# axiom_beta_shield_HDMI_v0_2_b03618a9.net
KiCad netlist of a schematic drawn in EAGLE
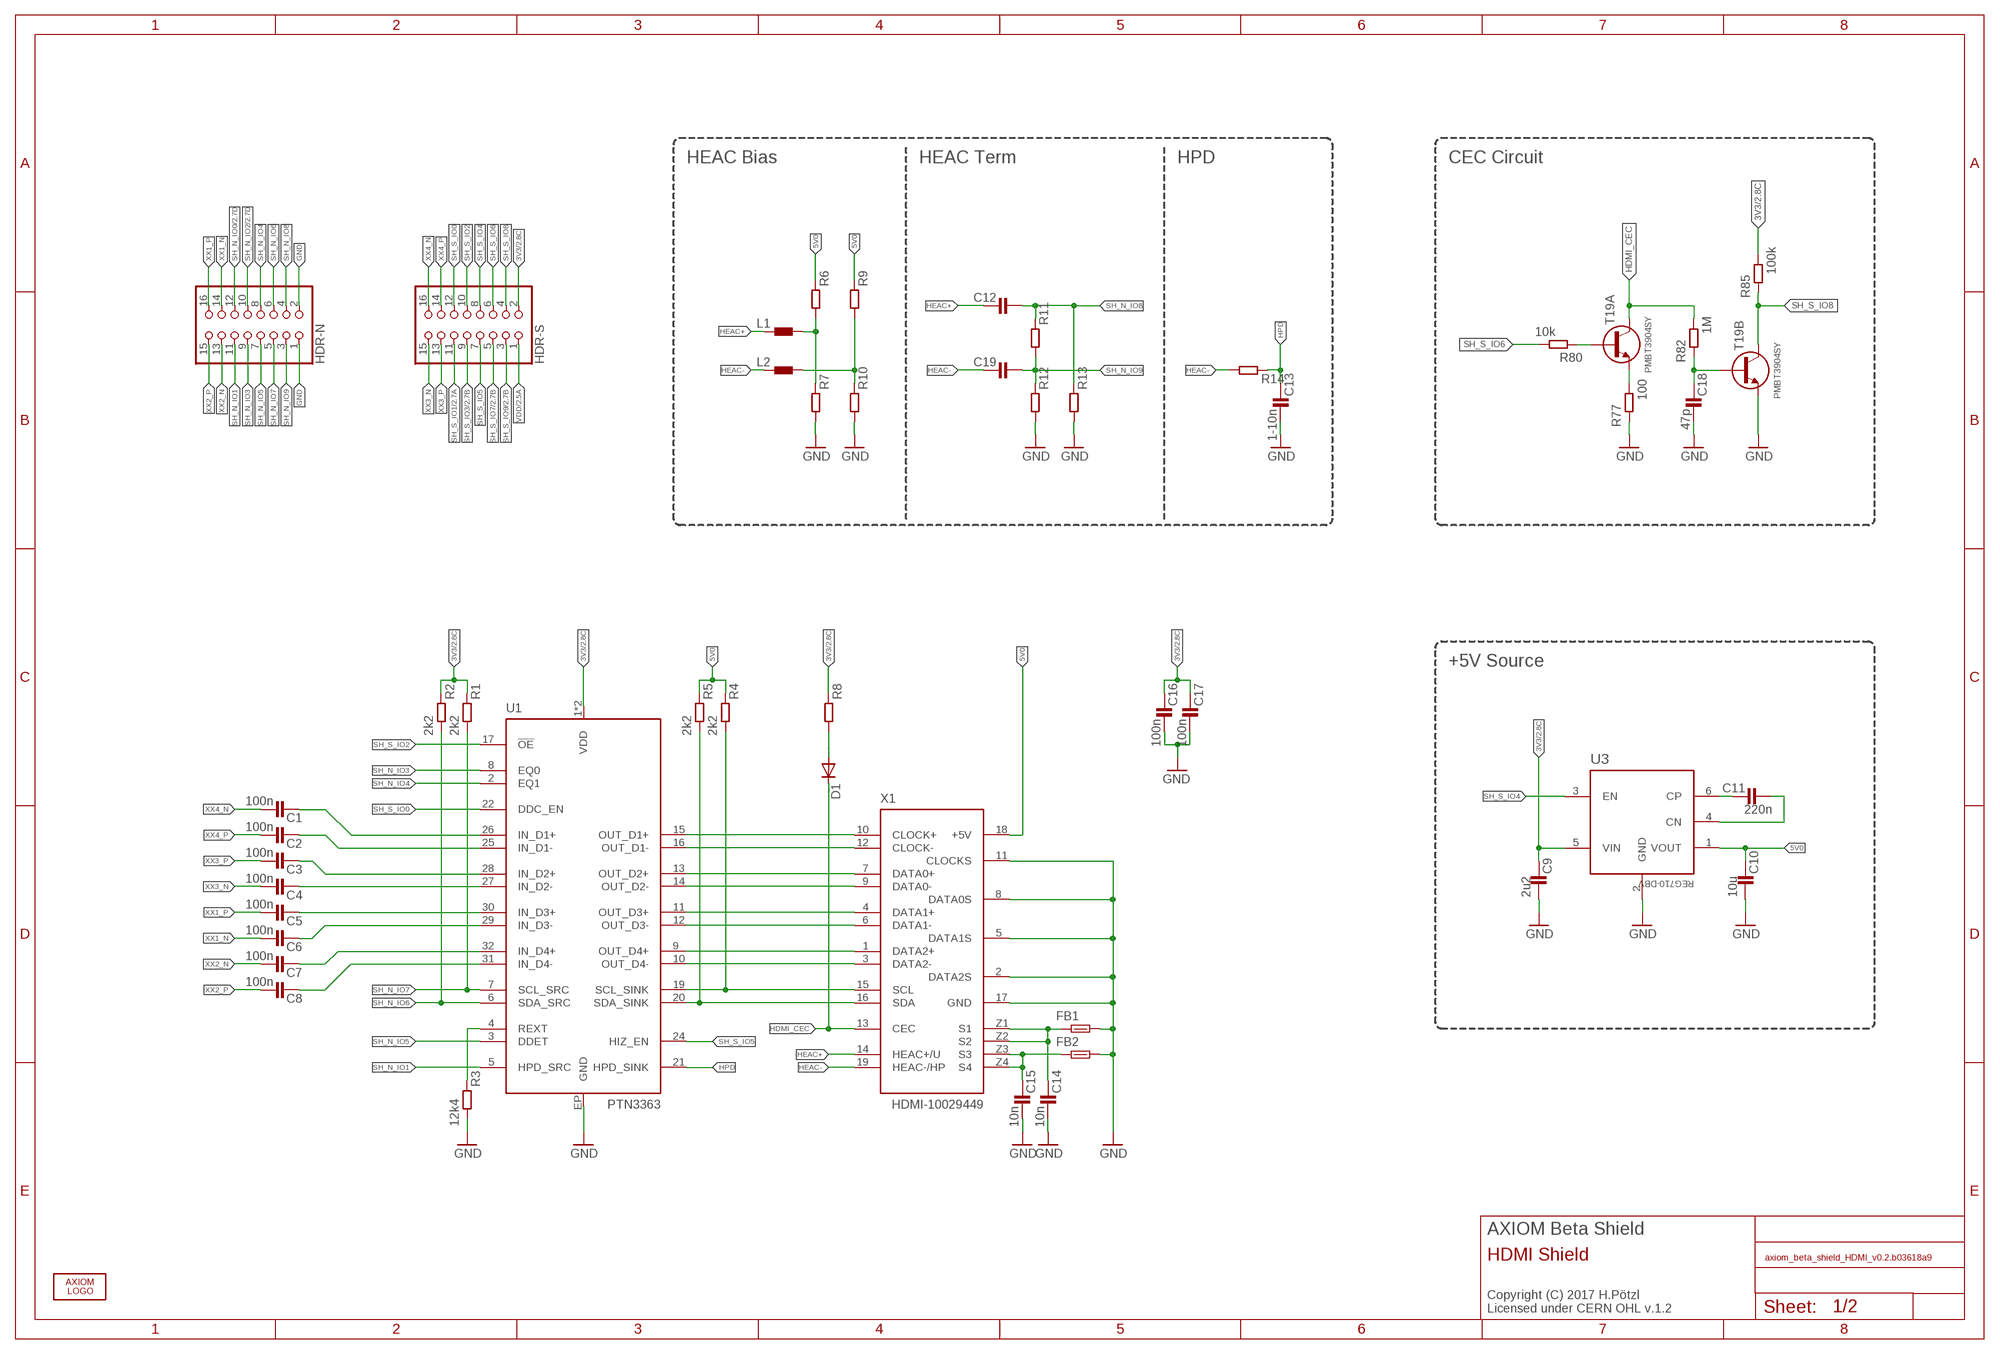
[diagram p0: schematic, sheet 1]
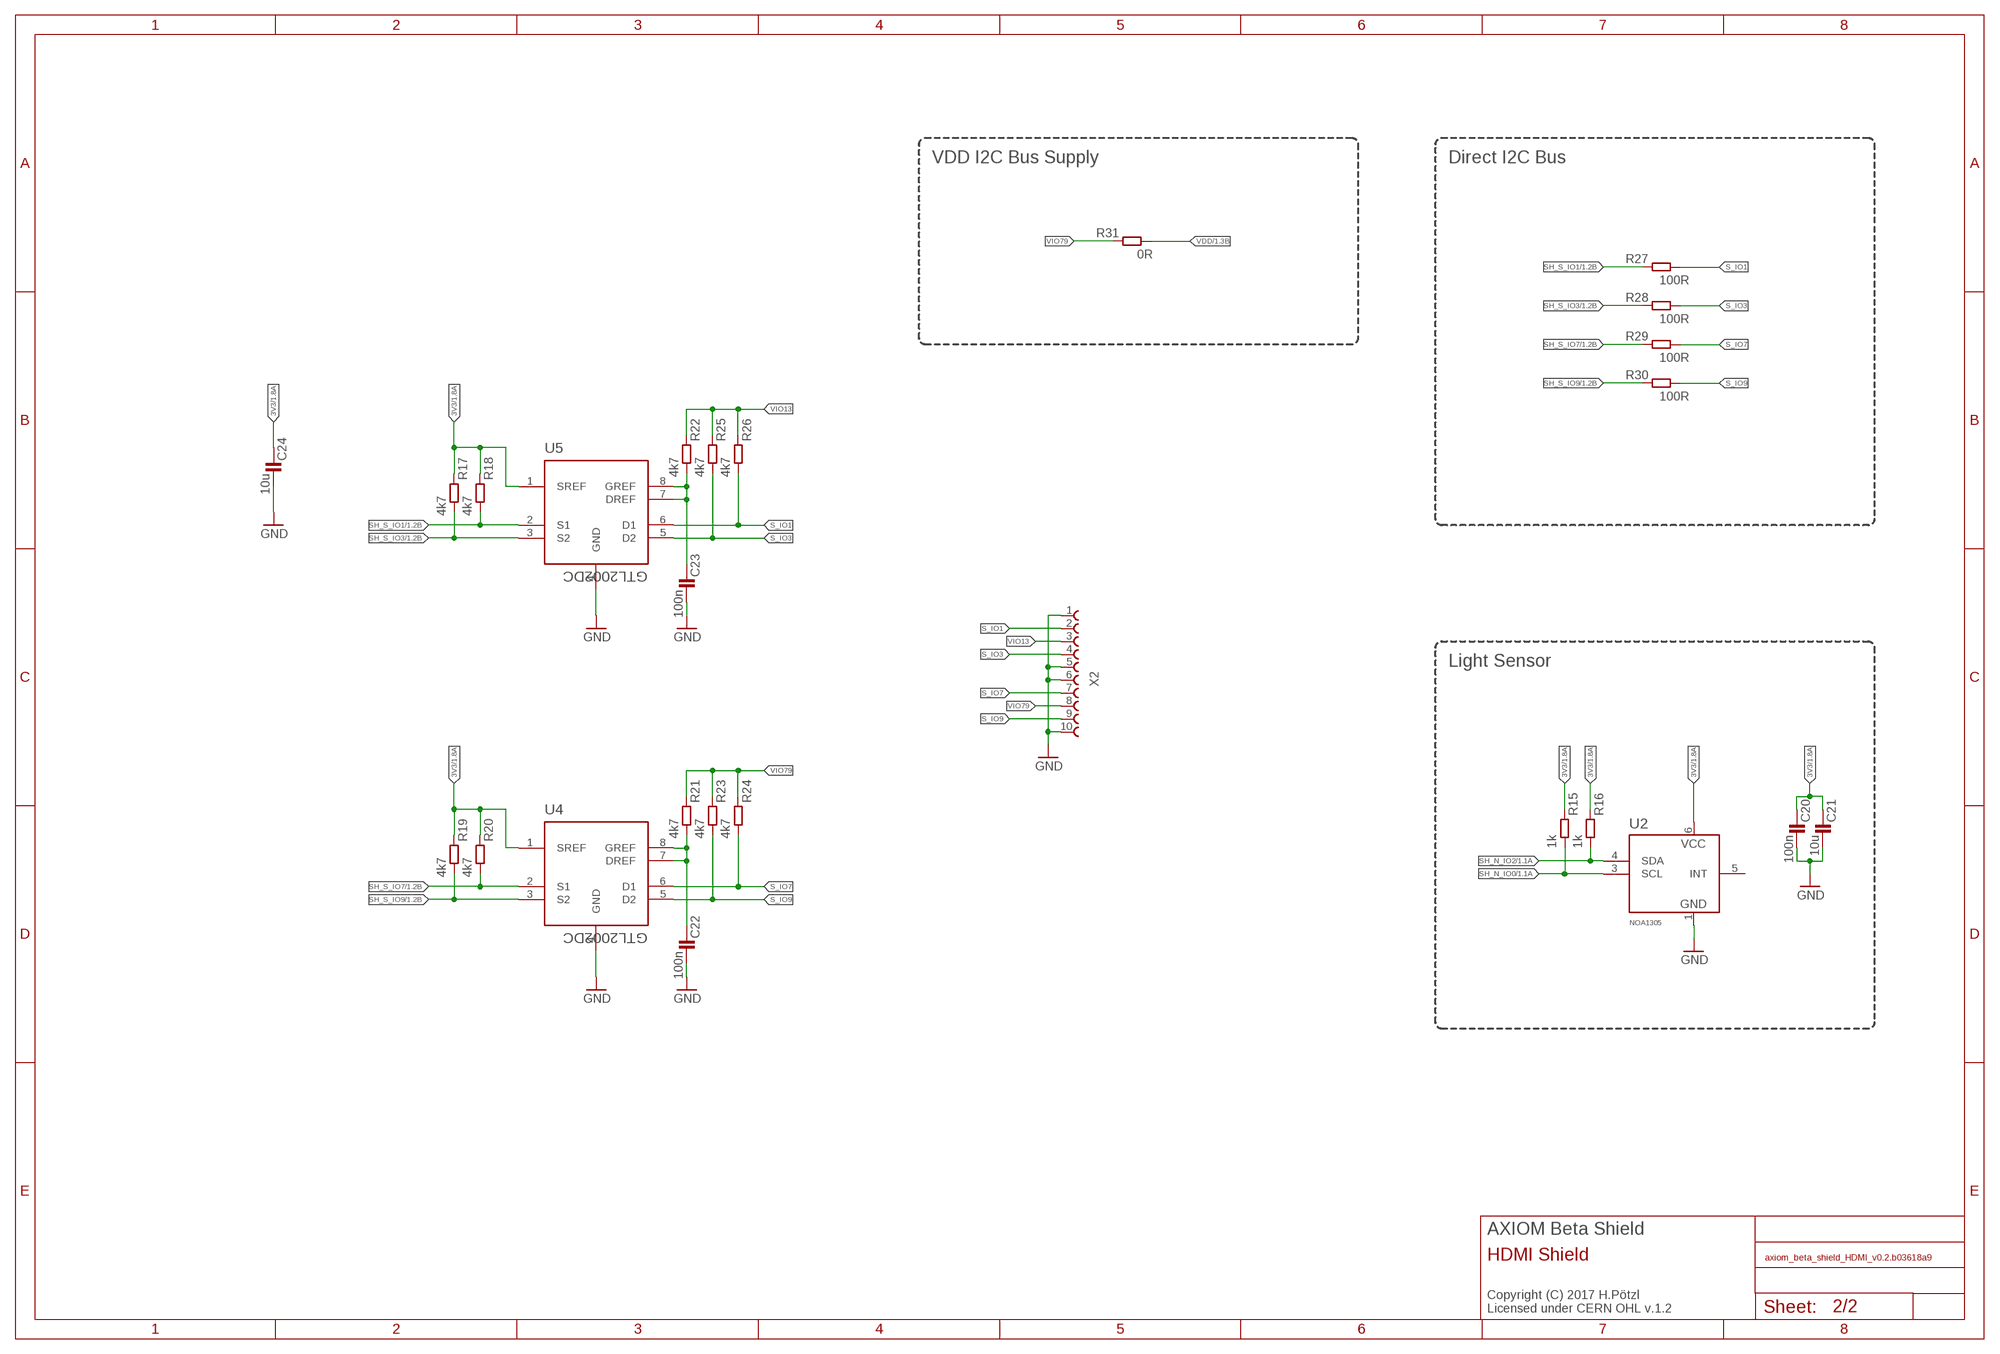
[diagram p1: schematic, sheet 2]

(export (version "E")
  (design (tool "Eeschema 10.0.6"))
  (components
    (comp (ref "C1")
      (value "100n")
      (footprint "eagle-import:0402-C")
      (libsource (lib "eagle-import") (part "C0402-C"))
    )
    (comp (ref "C2")
      (value "100n")
      (footprint "eagle-import:0402-C")
      (libsource (lib "eagle-import") (part "C0402-C"))
    )
    (comp (ref "C3")
      (value "100n")
      (footprint "eagle-import:0402-C")
      (libsource (lib "eagle-import") (part "C0402-C"))
    )
    (comp (ref "C4")
      (value "100n")
      (footprint "eagle-import:0402-C")
      (libsource (lib "eagle-import") (part "C0402-C"))
    )
    (comp (ref "C5")
      (value "100n")
      (footprint "eagle-import:0402-C")
      (libsource (lib "eagle-import") (part "C0402-C"))
    )
    (comp (ref "C6")
      (value "100n")
      (footprint "eagle-import:0402-C")
      (libsource (lib "eagle-import") (part "C0402-C"))
    )
    (comp (ref "C7")
      (value "100n")
      (footprint "eagle-import:0402-C")
      (libsource (lib "eagle-import") (part "C0402-C"))
    )
    (comp (ref "C8")
      (value "100n")
      (footprint "eagle-import:0402-C")
      (libsource (lib "eagle-import") (part "C0402-C"))
    )
    (comp (ref "C9")
      (value "2u2")
      (footprint "eagle-import:0603-B")
      (libsource (lib "eagle-import") (part "C0603-B"))
    )
    (comp (ref "C10")
      (value "10u")
      (footprint "eagle-import:0603-B")
      (libsource (lib "eagle-import") (part "C0603-B"))
    )
    (comp (ref "C11")
      (value "220n")
      (footprint "eagle-import:0402-B")
      (libsource (lib "eagle-import") (part "C0402-B"))
    )
    (comp (ref "C12")
      (value "C0402-B")
      (footprint "eagle-import:0402-B")
      (libsource (lib "eagle-import") (part "C0402-B"))
    )
    (comp (ref "C13")
      (value "1-10n")
      (footprint "eagle-import:0402-B")
      (libsource (lib "eagle-import") (part "C0402-B"))
    )
    (comp (ref "C14")
      (value "10n")
      (footprint "eagle-import:0402-B")
      (libsource (lib "eagle-import") (part "C0402-B"))
    )
    (comp (ref "C15")
      (value "10n")
      (footprint "eagle-import:0402-B")
      (libsource (lib "eagle-import") (part "C0402-B"))
    )
    (comp (ref "C16")
      (value "100n")
      (footprint "eagle-import:0402-B")
      (libsource (lib "eagle-import") (part "C0402-B"))
    )
    (comp (ref "C17")
      (value "100n")
      (footprint "eagle-import:0402-B")
      (libsource (lib "eagle-import") (part "C0402-B"))
    )
    (comp (ref "C18")
      (value "47p")
      (footprint "eagle-import:0402-B")
      (libsource (lib "eagle-import") (part "C0402-B"))
    )
    (comp (ref "C19")
      (value "C0402-B")
      (footprint "eagle-import:0402-B")
      (libsource (lib "eagle-import") (part "C0402-B"))
    )
    (comp (ref "D1")
      (value "DIODE-SOD523")
      (footprint "eagle-import:SOD523")
      (libsource (lib "eagle-import") (part "DIODE-SOD523"))
    )
    (comp (ref "FB1")
      (value "FB0603-B")
      (footprint "eagle-import:0603-B")
      (libsource (lib "eagle-import") (part "FB0603-B"))
    )
    (comp (ref "FB2")
      (value "FB0603-B")
      (footprint "eagle-import:0603-B")
      (libsource (lib "eagle-import") (part "FB0603-B"))
    )
    (comp (ref "HDR-N")
      (value "PINHD-2X08_2.00_SMD")
      (footprint "eagle-import:2X08M_SMD")
      (libsource (lib "eagle-import") (part "PINHD-2X08_2.00_SMD"))
    )
    (comp (ref "HDR-S")
      (value "PINHD-2X08_2.00_SMD")
      (footprint "eagle-import:2X08M_SMD")
      (libsource (lib "eagle-import") (part "PINHD-2X08_2.00_SMD"))
    )
    (comp (ref "L1")
      (value "L0402-B")
      (footprint "eagle-import:0402-B")
      (libsource (lib "eagle-import") (part "L0402-B"))
    )
    (comp (ref "L2")
      (value "L0402-B")
      (footprint "eagle-import:0402-B")
      (libsource (lib "eagle-import") (part "L0402-B"))
    )
    (comp (ref "R1")
      (value "2k2")
      (footprint "eagle-import:0402-B")
      (libsource (lib "eagle-import") (part "R0402-B"))
    )
    (comp (ref "R2")
      (value "2k2")
      (footprint "eagle-import:0402-B")
      (libsource (lib "eagle-import") (part "R0402-B"))
    )
    (comp (ref "R3")
      (value "12k4")
      (footprint "eagle-import:0402-B")
      (libsource (lib "eagle-import") (part "R0402-B"))
    )
    (comp (ref "R4")
      (value "2k2")
      (footprint "eagle-import:0402-B")
      (libsource (lib "eagle-import") (part "R0402-B"))
    )
    (comp (ref "R5")
      (value "2k2")
      (footprint "eagle-import:0402-B")
      (libsource (lib "eagle-import") (part "R0402-B"))
    )
    (comp (ref "R6")
      (value "R0402-B")
      (footprint "eagle-import:0402-B")
      (libsource (lib "eagle-import") (part "R0402-B"))
    )
    (comp (ref "R7")
      (value "R0402-B")
      (footprint "eagle-import:0402-B")
      (libsource (lib "eagle-import") (part "R0402-B"))
    )
    (comp (ref "R8")
      (value "R0402-B")
      (footprint "eagle-import:0402-B")
      (libsource (lib "eagle-import") (part "R0402-B"))
    )
    (comp (ref "R9")
      (value "R0402-B")
      (footprint "eagle-import:0402-B")
      (libsource (lib "eagle-import") (part "R0402-B"))
    )
    (comp (ref "R10")
      (value "R0402-B")
      (footprint "eagle-import:0402-B")
      (libsource (lib "eagle-import") (part "R0402-B"))
    )
    (comp (ref "R11")
      (value "R0402-B")
      (footprint "eagle-import:0402-B")
      (libsource (lib "eagle-import") (part "R0402-B"))
    )
    (comp (ref "R12")
      (value "R0402-B")
      (footprint "eagle-import:0402-B")
      (libsource (lib "eagle-import") (part "R0402-B"))
    )
    (comp (ref "R13")
      (value "R0402-B")
      (footprint "eagle-import:0402-B")
      (libsource (lib "eagle-import") (part "R0402-B"))
    )
    (comp (ref "R14")
      (value "R0402-B")
      (footprint "eagle-import:0402-B")
      (libsource (lib "eagle-import") (part "R0402-B"))
    )
    (comp (ref "R77")
      (value "100")
      (footprint "eagle-import:0402-B")
      (libsource (lib "eagle-import") (part "R0402-B"))
    )
    (comp (ref "R80")
      (value "10k")
      (footprint "eagle-import:0402-B")
      (libsource (lib "eagle-import") (part "R0402-B"))
    )
    (comp (ref "R82")
      (value "1M")
      (footprint "eagle-import:0402-B")
      (libsource (lib "eagle-import") (part "R0402-B"))
    )
    (comp (ref "R85")
      (value "100k")
      (footprint "eagle-import:0402-B")
      (libsource (lib "eagle-import") (part "R0402-B"))
    )
    (comp (ref "T19")
      (value "PMBT3904SY")
      (footprint "eagle-import:SOT363")
      (libsource (lib "eagle-import") (part "PMBT3904SY"))
    )
    (comp (ref "U$1")
      (value "AXIOM_LOGO459X70")
      (footprint "eagle-import:AXIOM_LOGO_459X70")
      (libsource (lib "eagle-import") (part "AXIOM_LOGO459X70"))
    )
    (comp (ref "U1")
      (value "PTN3363")
      (footprint "eagle-import:HVQFN32")
      (libsource (lib "eagle-import") (part "PTN3363"))
    )
    (comp (ref "U3")
      (value "REG710-DBV")
      (footprint "eagle-import:DBV")
      (libsource (lib "eagle-import") (part "REG710-DBV"))
    )
    (comp (ref "X1")
      (value "HDMI-10029449")
      (footprint "eagle-import:10029449-X01XLF")
      (libsource (lib "eagle-import") (part "HDMI-10029449"))
    )
    (comp (ref "C20")
      (value "100n")
      (footprint "eagle-import:0402-B")
      (libsource (lib "eagle-import") (part "C0402-B"))
    )
    (comp (ref "C21")
      (value "10u")
      (footprint "eagle-import:0402-B")
      (libsource (lib "eagle-import") (part "C0402-B"))
    )
    (comp (ref "C22")
      (value "100n")
      (footprint "eagle-import:0402-B")
      (libsource (lib "eagle-import") (part "C0402-B"))
    )
    (comp (ref "C23")
      (value "100n")
      (footprint "eagle-import:0402-B")
      (libsource (lib "eagle-import") (part "C0402-B"))
    )
    (comp (ref "C24")
      (value "10u")
      (footprint "eagle-import:0402-B")
      (libsource (lib "eagle-import") (part "C0402-B"))
    )
    (comp (ref "R15")
      (value "1k")
      (footprint "eagle-import:0402-B")
      (libsource (lib "eagle-import") (part "R0402-B"))
    )
    (comp (ref "R16")
      (value "1k")
      (footprint "eagle-import:0402-B")
      (libsource (lib "eagle-import") (part "R0402-B"))
    )
    (comp (ref "R17")
      (value "4k7")
      (footprint "eagle-import:0402-B")
      (libsource (lib "eagle-import") (part "R0402-B"))
    )
    (comp (ref "R18")
      (value "4k7")
      (footprint "eagle-import:0402-B")
      (libsource (lib "eagle-import") (part "R0402-B"))
    )
    (comp (ref "R19")
      (value "4k7")
      (footprint "eagle-import:0402-B")
      (libsource (lib "eagle-import") (part "R0402-B"))
    )
    (comp (ref "R20")
      (value "4k7")
      (footprint "eagle-import:0402-B")
      (libsource (lib "eagle-import") (part "R0402-B"))
    )
    (comp (ref "R21")
      (value "4k7")
      (footprint "eagle-import:0402-B")
      (libsource (lib "eagle-import") (part "R0402-B"))
    )
    (comp (ref "R22")
      (value "4k7")
      (footprint "eagle-import:0402-B")
      (libsource (lib "eagle-import") (part "R0402-B"))
    )
    (comp (ref "R23")
      (value "4k7")
      (footprint "eagle-import:0402-B")
      (libsource (lib "eagle-import") (part "R0402-B"))
    )
    (comp (ref "R24")
      (value "4k7")
      (footprint "eagle-import:0402-B")
      (libsource (lib "eagle-import") (part "R0402-B"))
    )
    (comp (ref "R25")
      (value "4k7")
      (footprint "eagle-import:0402-B")
      (libsource (lib "eagle-import") (part "R0402-B"))
    )
    (comp (ref "R26")
      (value "4k7")
      (footprint "eagle-import:0402-B")
      (libsource (lib "eagle-import") (part "R0402-B"))
    )
    (comp (ref "R27")
      (value "100R")
      (footprint "eagle-import:0402-B")
      (libsource (lib "eagle-import") (part "R0402-B"))
    )
    (comp (ref "R28")
      (value "100R")
      (footprint "eagle-import:0402-B")
      (libsource (lib "eagle-import") (part "R0402-B"))
    )
    (comp (ref "R29")
      (value "100R")
      (footprint "eagle-import:0402-B")
      (libsource (lib "eagle-import") (part "R0402-B"))
    )
    (comp (ref "R30")
      (value "100R")
      (footprint "eagle-import:0402-B")
      (libsource (lib "eagle-import") (part "R0402-B"))
    )
    (comp (ref "R31")
      (value "0R")
      (footprint "eagle-import:0402-B")
      (libsource (lib "eagle-import") (part "R0402-B"))
    )
    (comp (ref "U2")
      (value "NOA1305")
      (footprint "eagle-import:CUDFN6")
      (libsource (lib "eagle-import") (part "NOA1305"))
    )
    (comp (ref "U4")
      (value "GTL2002DC")
      (footprint "eagle-import:VSSOP-8")
      (libsource (lib "eagle-import") (part "GTL2002DC"))
    )
    (comp (ref "U5")
      (value "GTL2002DC")
      (footprint "eagle-import:VSSOP-8")
      (libsource (lib "eagle-import") (part "GTL2002DC"))
    )
    (comp (ref "X2")
      (value "68711014022")
      (footprint "eagle-import:68711014022")
      (libsource (lib "eagle-import") (part "68711014022"))
    )
  )
  (nets
    (net (code "1") (name "3V3") (class "Default")
      (node (ref "C16") (pin "1") (pinfunction "1_1") (pintype "passive"))
      (node (ref "C17") (pin "1") (pinfunction "1_1") (pintype "passive"))
      (node (ref "C20") (pin "1") (pinfunction "1_1") (pintype "passive"))
      (node (ref "C21") (pin "1") (pinfunction "1_1") (pintype "passive"))
      (node (ref "C24") (pin "1") (pinfunction "1_1") (pintype "passive"))
      (node (ref "C9") (pin "1") (pinfunction "1_1") (pintype "passive"))
      (node (ref "HDR-S") (pin "2") (pinfunction "2_2") (pintype "passive"))
      (node (ref "R1") (pin "1") (pinfunction "1_1") (pintype "passive"))
      (node (ref "R15") (pin "1") (pinfunction "1_1") (pintype "passive"))
      (node (ref "R16") (pin "1") (pinfunction "1_1") (pintype "passive"))
      (node (ref "R17") (pin "1") (pinfunction "1_1") (pintype "passive"))
      (node (ref "R18") (pin "1") (pinfunction "1_1") (pintype "passive"))
      (node (ref "R19") (pin "1") (pinfunction "1_1") (pintype "passive"))
      (node (ref "R2") (pin "1") (pinfunction "1_1") (pintype "passive"))
      (node (ref "R20") (pin "1") (pinfunction "1_1") (pintype "passive"))
      (node (ref "R8") (pin "1") (pinfunction "1_1") (pintype "passive"))
      (node (ref "R85") (pin "2") (pinfunction "2_2") (pintype "passive"))
      (node (ref "U1") (pin "1") (pinfunction "VDD_1") (pintype "power_in"))
      (node (ref "U1") (pin "18") (pinfunction "VDD_18") (pintype "power_in"))
      (node (ref "U2") (pin "6") (pinfunction "VCC_6") (pintype "power_in"))
      (node (ref "U3") (pin "5") (pinfunction "VIN_5") (pintype "power_in"))
      (node (ref "U4") (pin "1") (pinfunction "SREF_1") (pintype "passive"))
      (node (ref "U5") (pin "1") (pinfunction "SREF_1") (pintype "passive"))
    )
    (net (code "2") (name "5V0") (class "Default")
      (node (ref "C10") (pin "1") (pinfunction "1_1") (pintype "passive"))
      (node (ref "R4") (pin "1") (pinfunction "1_1") (pintype "passive"))
      (node (ref "R5") (pin "1") (pinfunction "1_1") (pintype "passive"))
      (node (ref "R6") (pin "1") (pinfunction "1_1") (pintype "passive"))
      (node (ref "R9") (pin "1") (pinfunction "1_1") (pintype "passive"))
      (node (ref "U3") (pin "1") (pinfunction "VOUT_1") (pintype "output"))
      (node (ref "X1") (pin "18") (pinfunction "+5V_18") (pintype "power_in"))
    )
    (net (code "3") (name "GND") (class "Default")
      (node (ref "C10") (pin "2") (pinfunction "2_2") (pintype "passive"))
      (node (ref "C13") (pin "2") (pinfunction "2_2") (pintype "passive"))
      (node (ref "C14") (pin "2") (pinfunction "2_2") (pintype "passive"))
      (node (ref "C15") (pin "2") (pinfunction "2_2") (pintype "passive"))
      (node (ref "C16") (pin "2") (pinfunction "2_2") (pintype "passive"))
      (node (ref "C17") (pin "2") (pinfunction "2_2") (pintype "passive"))
      (node (ref "C18") (pin "2") (pinfunction "2_2") (pintype "passive"))
      (node (ref "C20") (pin "2") (pinfunction "2_2") (pintype "passive"))
      (node (ref "C21") (pin "2") (pinfunction "2_2") (pintype "passive"))
      (node (ref "C22") (pin "2") (pinfunction "2_2") (pintype "passive"))
      (node (ref "C23") (pin "2") (pinfunction "2_2") (pintype "passive"))
      (node (ref "C24") (pin "2") (pinfunction "2_2") (pintype "passive"))
      (node (ref "C9") (pin "2") (pinfunction "2_2") (pintype "passive"))
      (node (ref "FB1") (pin "2") (pinfunction "2_2") (pintype "passive"))
      (node (ref "FB2") (pin "2") (pinfunction "2_2") (pintype "passive"))
      (node (ref "HDR-N") (pin "1") (pinfunction "1_1") (pintype "passive"))
      (node (ref "HDR-N") (pin "2") (pinfunction "2_2") (pintype "passive"))
      (node (ref "R10") (pin "2") (pinfunction "2_2") (pintype "passive"))
      (node (ref "R12") (pin "2") (pinfunction "2_2") (pintype "passive"))
      (node (ref "R13") (pin "2") (pinfunction "2_2") (pintype "passive"))
      (node (ref "R3") (pin "2") (pinfunction "2_2") (pintype "passive"))
      (node (ref "R7") (pin "2") (pinfunction "2_2") (pintype "passive"))
      (node (ref "R77") (pin "1") (pinfunction "1_1") (pintype "passive"))
      (node (ref "T19") (pin "4") (pinfunction "E_4") (pintype "passive"))
      (node (ref "U1") (pin "EP") (pinfunction "GND_EP") (pintype "bidirectional"))
      (node (ref "U2") (pin "1") (pinfunction "VSS_1") (pintype "power_in"))
      (node (ref "U3") (pin "2") (pinfunction "GND_2") (pintype "passive"))
      (node (ref "U4") (pin "4") (pinfunction "GND_4") (pintype "passive"))
      (node (ref "U5") (pin "4") (pinfunction "GND_4") (pintype "passive"))
      (node (ref "X1") (pin "11") (pinfunction "CLOCKS_11") (pintype "power_in"))
      (node (ref "X1") (pin "17") (pinfunction "GND_17") (pintype "bidirectional"))
      (node (ref "X1") (pin "2") (pinfunction "DATA2S_2") (pintype "power_in"))
      (node (ref "X1") (pin "5") (pinfunction "DATA1S_5") (pintype "power_in"))
      (node (ref "X1") (pin "8") (pinfunction "DATA0S_8") (pintype "power_in"))
      (node (ref "X2") (pin "1") (pinfunction "1_1") (pintype "passive"))
      (node (ref "X2") (pin "10") (pinfunction "10_10") (pintype "passive"))
      (node (ref "X2") (pin "5") (pinfunction "5_5") (pintype "passive"))
      (node (ref "X2") (pin "6") (pinfunction "6_6") (pintype "passive"))
    )
    (net (code "4") (name "HDMI_CEC") (class "Default")
      (node (ref "D1") (pin "C") (pinfunction "C_C") (pintype "passive"))
      (node (ref "R82") (pin "2") (pinfunction "2_2") (pintype "passive"))
      (node (ref "T19") (pin "6") (pinfunction "C_6") (pintype "passive"))
      (node (ref "X1") (pin "13") (pinfunction "CEC_13") (pintype "bidirectional"))
    )
    (net (code "5") (name "HEAC+") (class "Default")
      (node (ref "C12") (pin "1") (pinfunction "1_1") (pintype "passive"))
      (node (ref "L1") (pin "1") (pinfunction "1_1") (pintype "passive"))
      (node (ref "X1") (pin "14") (pinfunction "HEAC+/U_14") (pintype "bidirectional"))
    )
    (net (code "6") (name "HEAC-") (class "Default")
      (node (ref "C19") (pin "1") (pinfunction "1_1") (pintype "passive"))
      (node (ref "L2") (pin "1") (pinfunction "1_1") (pintype "passive"))
      (node (ref "R14") (pin "2") (pinfunction "2_2") (pintype "passive"))
      (node (ref "X1") (pin "19") (pinfunction "HEAC-/HP_19") (pintype "bidirectional"))
    )
    (net (code "7") (name "HPD") (class "Default")
      (node (ref "C13") (pin "1") (pinfunction "1_1") (pintype "passive"))
      (node (ref "R14") (pin "1") (pinfunction "1_1") (pintype "passive"))
      (node (ref "U1") (pin "21") (pinfunction "HPD_SINK_21") (pintype "bidirectional"))
    )
    (net (code "8") (name "Net-(D1-PadA)") (class "Default")
      (node (ref "D1") (pin "A") (pinfunction "A_A") (pintype "passive"))
      (node (ref "R8") (pin "2") (pinfunction "2_2") (pintype "passive"))
    )
    (net (code "9") (name "Net-(L1-Pad2)") (class "Default")
      (node (ref "L1") (pin "2") (pinfunction "2_2") (pintype "passive"))
      (node (ref "R6") (pin "2") (pinfunction "2_2") (pintype "passive"))
      (node (ref "R7") (pin "1") (pinfunction "1_1") (pintype "passive"))
    )
    (net (code "10") (name "Net-(L2-Pad2)") (class "Default")
      (node (ref "L2") (pin "2") (pinfunction "2_2") (pintype "passive"))
      (node (ref "R10") (pin "1") (pinfunction "1_1") (pintype "passive"))
      (node (ref "R9") (pin "2") (pinfunction "2_2") (pintype "passive"))
    )
    (net (code "11") (name "Net-(T19A-B)") (class "Default")
      (node (ref "R80") (pin "1") (pinfunction "1_1") (pintype "passive"))
      (node (ref "T19") (pin "2") (pinfunction "B_2") (pintype "passive"))
    )
    (net (code "12") (name "Net-(T19A-E)") (class "Default")
      (node (ref "R77") (pin "2") (pinfunction "2_2") (pintype "passive"))
      (node (ref "T19") (pin "1") (pinfunction "E_1") (pintype "passive"))
    )
    (net (code "13") (name "Net-(T19B-B)") (class "Default")
      (node (ref "C18") (pin "1") (pinfunction "1_1") (pintype "passive"))
      (node (ref "R82") (pin "1") (pinfunction "1_1") (pintype "passive"))
      (node (ref "T19") (pin "5") (pinfunction "B_5") (pintype "passive"))
    )
    (net (code "14") (name "Net-(U1-IN_D1+)") (class "Default")
      (node (ref "C1") (pin "1") (pinfunction "1_1") (pintype "passive"))
      (node (ref "U1") (pin "26") (pinfunction "IN_D1+_26") (pintype "bidirectional"))
    )
    (net (code "15") (name "Net-(U1-IN_D1-)") (class "Default")
      (node (ref "C2") (pin "1") (pinfunction "1_1") (pintype "passive"))
      (node (ref "U1") (pin "25") (pinfunction "IN_D1-_25") (pintype "bidirectional"))
    )
    (net (code "16") (name "Net-(U1-IN_D2+)") (class "Default")
      (node (ref "C3") (pin "1") (pinfunction "1_1") (pintype "passive"))
      (node (ref "U1") (pin "28") (pinfunction "IN_D2+_28") (pintype "bidirectional"))
    )
    (net (code "17") (name "Net-(U1-IN_D2-)") (class "Default")
      (node (ref "C4") (pin "1") (pinfunction "1_1") (pintype "passive"))
      (node (ref "U1") (pin "27") (pinfunction "IN_D2-_27") (pintype "bidirectional"))
    )
    (net (code "18") (name "Net-(U1-IN_D3+)") (class "Default")
      (node (ref "C5") (pin "1") (pinfunction "1_1") (pintype "passive"))
      (node (ref "U1") (pin "30") (pinfunction "IN_D3+_30") (pintype "bidirectional"))
    )
    (net (code "19") (name "Net-(U1-IN_D3-)") (class "Default")
      (node (ref "C6") (pin "1") (pinfunction "1_1") (pintype "passive"))
      (node (ref "U1") (pin "29") (pinfunction "IN_D3-_29") (pintype "bidirectional"))
    )
    (net (code "20") (name "Net-(U1-IN_D4+)") (class "Default")
      (node (ref "C7") (pin "1") (pinfunction "1_1") (pintype "passive"))
      (node (ref "U1") (pin "32") (pinfunction "IN_D4+_32") (pintype "bidirectional"))
    )
    (net (code "21") (name "Net-(U1-IN_D4-)") (class "Default")
      (node (ref "C8") (pin "1") (pinfunction "1_1") (pintype "passive"))
      (node (ref "U1") (pin "31") (pinfunction "IN_D4-_31") (pintype "bidirectional"))
    )
    (net (code "22") (name "Net-(U1-OUT_D1+)") (class "Default")
      (node (ref "U1") (pin "15") (pinfunction "OUT_D1+_15") (pintype "bidirectional"))
      (node (ref "X1") (pin "10") (pinfunction "CLOCK+_10") (pintype "bidirectional"))
    )
    (net (code "23") (name "Net-(U1-OUT_D1-)") (class "Default")
      (node (ref "U1") (pin "16") (pinfunction "OUT_D1-_16") (pintype "bidirectional"))
      (node (ref "X1") (pin "12") (pinfunction "CLOCK-_12") (pintype "bidirectional"))
    )
    (net (code "24") (name "Net-(U1-OUT_D2+)") (class "Default")
      (node (ref "U1") (pin "13") (pinfunction "OUT_D2+_13") (pintype "bidirectional"))
      (node (ref "X1") (pin "7") (pinfunction "DATA0+_7") (pintype "bidirectional"))
    )
    (net (code "25") (name "Net-(U1-OUT_D2-)") (class "Default")
      (node (ref "U1") (pin "14") (pinfunction "OUT_D2-_14") (pintype "bidirectional"))
      (node (ref "X1") (pin "9") (pinfunction "DATA0-_9") (pintype "bidirectional"))
    )
    (net (code "26") (name "Net-(U1-OUT_D3+)") (class "Default")
      (node (ref "U1") (pin "11") (pinfunction "OUT_D3+_11") (pintype "bidirectional"))
      (node (ref "X1") (pin "4") (pinfunction "DATA1+_4") (pintype "bidirectional"))
    )
    (net (code "27") (name "Net-(U1-OUT_D3-)") (class "Default")
      (node (ref "U1") (pin "12") (pinfunction "OUT_D3-_12") (pintype "bidirectional"))
      (node (ref "X1") (pin "6") (pinfunction "DATA1-_6") (pintype "bidirectional"))
    )
    (net (code "28") (name "Net-(U1-OUT_D4+)") (class "Default")
      (node (ref "U1") (pin "9") (pinfunction "OUT_D4+_9") (pintype "bidirectional"))
      (node (ref "X1") (pin "1") (pinfunction "DATA2+_1") (pintype "bidirectional"))
    )
    (net (code "29") (name "Net-(U1-OUT_D4-)") (class "Default")
      (node (ref "U1") (pin "10") (pinfunction "OUT_D4-_10") (pintype "bidirectional"))
      (node (ref "X1") (pin "3") (pinfunction "DATA2-_3") (pintype "bidirectional"))
    )
    (net (code "30") (name "Net-(U1-REXT)") (class "Default")
      (node (ref "R3") (pin "1") (pinfunction "1_1") (pintype "passive"))
      (node (ref "U1") (pin "4") (pinfunction "REXT_4") (pintype "bidirectional"))
    )
    (net (code "31") (name "Net-(U1-SCL_SINK)") (class "Default")
      (node (ref "R4") (pin "2") (pinfunction "2_2") (pintype "passive"))
      (node (ref "U1") (pin "19") (pinfunction "SCL_SINK_19") (pintype "bidirectional"))
      (node (ref "X1") (pin "15") (pinfunction "SCL_15") (pintype "bidirectional"))
    )
    (net (code "32") (name "Net-(U1-SDA_SINK)") (class "Default")
      (node (ref "R5") (pin "2") (pinfunction "2_2") (pintype "passive"))
      (node (ref "U1") (pin "20") (pinfunction "SDA_SINK_20") (pintype "bidirectional"))
      (node (ref "X1") (pin "16") (pinfunction "SDA_16") (pintype "bidirectional"))
    )
    (net (code "33") (name "Net-(U3-CN)") (class "Default")
      (node (ref "C11") (pin "2") (pinfunction "2_2") (pintype "passive"))
      (node (ref "U3") (pin "4") (pinfunction "CN_4") (pintype "power_in"))
    )
    (net (code "34") (name "Net-(U3-CP)") (class "Default")
      (node (ref "C11") (pin "1") (pinfunction "1_1") (pintype "passive"))
      (node (ref "U3") (pin "6") (pinfunction "CP_6") (pintype "output"))
    )
    (net (code "35") (name "Net-(U4-DREF)") (class "Default")
      (node (ref "C22") (pin "1") (pinfunction "1_1") (pintype "passive"))
      (node (ref "R21") (pin "2") (pinfunction "2_2") (pintype "passive"))
      (node (ref "U4") (pin "7") (pinfunction "DREF_7") (pintype "passive"))
      (node (ref "U4") (pin "8") (pinfunction "GREF_8") (pintype "passive"))
    )
    (net (code "36") (name "Net-(U5-DREF)") (class "Default")
      (node (ref "C23") (pin "1") (pinfunction "1_1") (pintype "passive"))
      (node (ref "R22") (pin "2") (pinfunction "2_2") (pintype "passive"))
      (node (ref "U5") (pin "7") (pinfunction "DREF_7") (pintype "passive"))
      (node (ref "U5") (pin "8") (pinfunction "GREF_8") (pintype "passive"))
    )
    (net (code "37") (name "Net-(X1-S1)") (class "Default")
      (node (ref "C14") (pin "1") (pinfunction "1_1") (pintype "passive"))
      (node (ref "FB1") (pin "1") (pinfunction "1_1") (pintype "passive"))
      (node (ref "X1") (pin "Z1") (pinfunction "S1_Z1") (pintype "power_in"))
      (node (ref "X1") (pin "Z2") (pinfunction "S2_Z2") (pintype "power_in"))
    )
    (net (code "38") (name "Net-(X1-S3)") (class "Default")
      (node (ref "C15") (pin "1") (pinfunction "1_1") (pintype "passive"))
      (node (ref "FB2") (pin "1") (pinfunction "1_1") (pintype "passive"))
      (node (ref "X1") (pin "Z3") (pinfunction "S3_Z3") (pintype "power_in"))
      (node (ref "X1") (pin "Z4") (pinfunction "S4_Z4") (pintype "power_in"))
    )
    (net (code "39") (name "SH_N_IO0") (class "Default")
      (node (ref "HDR-N") (pin "12") (pinfunction "12_12") (pintype "passive"))
      (node (ref "R15") (pin "2") (pinfunction "2_2") (pintype "passive"))
      (node (ref "U2") (pin "3") (pinfunction "SCL_3") (pintype "bidirectional"))
    )
    (net (code "40") (name "SH_N_IO1") (class "Default")
      (node (ref "HDR-N") (pin "11") (pinfunction "11_11") (pintype "passive"))
      (node (ref "U1") (pin "5") (pinfunction "HPD_SRC_5") (pintype "bidirectional"))
    )
    (net (code "41") (name "SH_N_IO2") (class "Default")
      (node (ref "HDR-N") (pin "10") (pinfunction "10_10") (pintype "passive"))
      (node (ref "R16") (pin "2") (pinfunction "2_2") (pintype "passive"))
      (node (ref "U2") (pin "4") (pinfunction "SDA_4") (pintype "bidirectional"))
    )
    (net (code "42") (name "SH_N_IO3") (class "Default")
      (node (ref "HDR-N") (pin "9") (pinfunction "9_9") (pintype "passive"))
      (node (ref "U1") (pin "8") (pinfunction "EQ0_8") (pintype "bidirectional"))
    )
    (net (code "43") (name "SH_N_IO4") (class "Default")
      (node (ref "HDR-N") (pin "8") (pinfunction "8_8") (pintype "passive"))
      (node (ref "U1") (pin "2") (pinfunction "EQ1_2") (pintype "bidirectional"))
    )
    (net (code "44") (name "SH_N_IO5") (class "Default")
      (node (ref "HDR-N") (pin "7") (pinfunction "7_7") (pintype "passive"))
      (node (ref "U1") (pin "3") (pinfunction "DDET_3") (pintype "bidirectional"))
    )
    (net (code "45") (name "SH_N_IO6") (class "Default")
      (node (ref "HDR-N") (pin "6") (pinfunction "6_6") (pintype "passive"))
      (node (ref "R2") (pin "2") (pinfunction "2_2") (pintype "passive"))
      (node (ref "U1") (pin "6") (pinfunction "SDA_SRC_6") (pintype "bidirectional"))
    )
    (net (code "46") (name "SH_N_IO7") (class "Default")
      (node (ref "HDR-N") (pin "5") (pinfunction "5_5") (pintype "passive"))
      (node (ref "R1") (pin "2") (pinfunction "2_2") (pintype "passive"))
      (node (ref "U1") (pin "7") (pinfunction "SCL_SRC_7") (pintype "bidirectional"))
    )
    (net (code "47") (name "SH_N_IO8") (class "Default")
      (node (ref "C12") (pin "2") (pinfunction "2_2") (pintype "passive"))
      (node (ref "HDR-N") (pin "4") (pinfunction "4_4") (pintype "passive"))
      (node (ref "R11") (pin "1") (pinfunction "1_1") (pintype "passive"))
      (node (ref "R13") (pin "1") (pinfunction "1_1") (pintype "passive"))
    )
    (net (code "48") (name "SH_N_IO9") (class "Default")
      (node (ref "C19") (pin "2") (pinfunction "2_2") (pintype "passive"))
      (node (ref "HDR-N") (pin "3") (pinfunction "3_3") (pintype "passive"))
      (node (ref "R11") (pin "2") (pinfunction "2_2") (pintype "passive"))
      (node (ref "R12") (pin "1") (pinfunction "1_1") (pintype "passive"))
    )
    (net (code "49") (name "SH_S_IO0") (class "Default")
      (node (ref "HDR-S") (pin "12") (pinfunction "12_12") (pintype "passive"))
      (node (ref "U1") (pin "22") (pinfunction "DDC_EN_22") (pintype "bidirectional"))
    )
    (net (code "50") (name "SH_S_IO1") (class "Default")
      (node (ref "HDR-S") (pin "11") (pinfunction "11_11") (pintype "passive"))
      (node (ref "R18") (pin "2") (pinfunction "2_2") (pintype "passive"))
      (node (ref "R27") (pin "1") (pinfunction "1_1") (pintype "passive"))
      (node (ref "U5") (pin "2") (pinfunction "S1_2") (pintype "bidirectional"))
    )
    (net (code "51") (name "SH_S_IO2") (class "Default")
      (node (ref "HDR-S") (pin "10") (pinfunction "10_10") (pintype "passive"))
      (node (ref "U1") (pin "17") (pinfunction "~{OE}_17") (pintype "bidirectional"))
    )
    (net (code "52") (name "SH_S_IO3") (class "Default")
      (node (ref "HDR-S") (pin "9") (pinfunction "9_9") (pintype "passive"))
      (node (ref "R17") (pin "2") (pinfunction "2_2") (pintype "passive"))
      (node (ref "R28") (pin "1") (pinfunction "1_1") (pintype "passive"))
      (node (ref "U5") (pin "3") (pinfunction "S2_3") (pintype "bidirectional"))
    )
    (net (code "53") (name "SH_S_IO4") (class "Default")
      (node (ref "HDR-S") (pin "8") (pinfunction "8_8") (pintype "passive"))
      (node (ref "U3") (pin "3") (pinfunction "EN_3") (pintype "input"))
    )
    (net (code "54") (name "SH_S_IO5") (class "Default")
      (node (ref "HDR-S") (pin "7") (pinfunction "7_7") (pintype "passive"))
      (node (ref "U1") (pin "24") (pinfunction "HIZ_EN_24") (pintype "bidirectional"))
    )
    (net (code "55") (name "SH_S_IO6") (class "Default")
      (node (ref "HDR-S") (pin "6") (pinfunction "6_6") (pintype "passive"))
      (node (ref "R80") (pin "2") (pinfunction "2_2") (pintype "passive"))
    )
    (net (code "56") (name "SH_S_IO7") (class "Default")
      (node (ref "HDR-S") (pin "5") (pinfunction "5_5") (pintype "passive"))
      (node (ref "R20") (pin "2") (pinfunction "2_2") (pintype "passive"))
      (node (ref "R29") (pin "1") (pinfunction "1_1") (pintype "passive"))
      (node (ref "U4") (pin "2") (pinfunction "S1_2") (pintype "bidirectional"))
    )
    (net (code "57") (name "SH_S_IO8") (class "Default")
      (node (ref "HDR-S") (pin "4") (pinfunction "4_4") (pintype "passive"))
      (node (ref "R85") (pin "1") (pinfunction "1_1") (pintype "passive"))
      (node (ref "T19") (pin "3") (pinfunction "C_3") (pintype "passive"))
    )
    (net (code "58") (name "SH_S_IO9") (class "Default")
      (node (ref "HDR-S") (pin "3") (pinfunction "3_3") (pintype "passive"))
      (node (ref "R19") (pin "2") (pinfunction "2_2") (pintype "passive"))
      (node (ref "R30") (pin "1") (pinfunction "1_1") (pintype "passive"))
      (node (ref "U4") (pin "3") (pinfunction "S2_3") (pintype "bidirectional"))
    )
    (net (code "59") (name "S_IO1") (class "Default")
      (node (ref "R26") (pin "2") (pinfunction "2_2") (pintype "passive"))
      (node (ref "R27") (pin "2") (pinfunction "2_2") (pintype "passive"))
      (node (ref "U5") (pin "6") (pinfunction "D1_6") (pintype "bidirectional"))
      (node (ref "X2") (pin "2") (pinfunction "2_2") (pintype "passive"))
    )
    (net (code "60") (name "S_IO3") (class "Default")
      (node (ref "R25") (pin "2") (pinfunction "2_2") (pintype "passive"))
      (node (ref "R28") (pin "2") (pinfunction "2_2") (pintype "passive"))
      (node (ref "U5") (pin "5") (pinfunction "D2_5") (pintype "bidirectional"))
      (node (ref "X2") (pin "4") (pinfunction "4_4") (pintype "passive"))
    )
    (net (code "61") (name "S_IO7") (class "Default")
      (node (ref "R24") (pin "2") (pinfunction "2_2") (pintype "passive"))
      (node (ref "R29") (pin "2") (pinfunction "2_2") (pintype "passive"))
      (node (ref "U4") (pin "6") (pinfunction "D1_6") (pintype "bidirectional"))
      (node (ref "X2") (pin "7") (pinfunction "7_7") (pintype "passive"))
    )
    (net (code "62") (name "S_IO9") (class "Default")
      (node (ref "R23") (pin "2") (pinfunction "2_2") (pintype "passive"))
      (node (ref "R30") (pin "2") (pinfunction "2_2") (pintype "passive"))
      (node (ref "U4") (pin "5") (pinfunction "D2_5") (pintype "bidirectional"))
      (node (ref "X2") (pin "9") (pinfunction "9_9") (pintype "passive"))
    )
    (net (code "63") (name "VDD") (class "Default")
      (node (ref "HDR-S") (pin "1") (pinfunction "1_1") (pintype "passive"))
      (node (ref "R31") (pin "2") (pinfunction "2_2") (pintype "passive"))
    )
    (net (code "64") (name "VIO13") (class "Default")
      (node (ref "R22") (pin "1") (pinfunction "1_1") (pintype "passive"))
      (node (ref "R25") (pin "1") (pinfunction "1_1") (pintype "passive"))
      (node (ref "R26") (pin "1") (pinfunction "1_1") (pintype "passive"))
      (node (ref "X2") (pin "3") (pinfunction "3_3") (pintype "passive"))
    )
    (net (code "65") (name "VIO79") (class "Default")
      (node (ref "R21") (pin "1") (pinfunction "1_1") (pintype "passive"))
      (node (ref "R23") (pin "1") (pinfunction "1_1") (pintype "passive"))
      (node (ref "R24") (pin "1") (pinfunction "1_1") (pintype "passive"))
      (node (ref "R31") (pin "1") (pinfunction "1_1") (pintype "passive"))
      (node (ref "X2") (pin "8") (pinfunction "8_8") (pintype "passive"))
    )
    (net (code "66") (name "XX1_N") (class "Default")
      (node (ref "C6") (pin "2") (pinfunction "2_2") (pintype "passive"))
      (node (ref "HDR-N") (pin "14") (pinfunction "14_14") (pintype "passive"))
    )
    (net (code "67") (name "XX1_P") (class "Default")
      (node (ref "C5") (pin "2") (pinfunction "2_2") (pintype "passive"))
      (node (ref "HDR-N") (pin "16") (pinfunction "16_16") (pintype "passive"))
    )
    (net (code "68") (name "XX2_N") (class "Default")
      (node (ref "C7") (pin "2") (pinfunction "2_2") (pintype "passive"))
      (node (ref "HDR-N") (pin "13") (pinfunction "13_13") (pintype "passive"))
    )
    (net (code "69") (name "XX2_P") (class "Default")
      (node (ref "C8") (pin "2") (pinfunction "2_2") (pintype "passive"))
      (node (ref "HDR-N") (pin "15") (pinfunction "15_15") (pintype "passive"))
    )
    (net (code "70") (name "XX3_N") (class "Default")
      (node (ref "C4") (pin "2") (pinfunction "2_2") (pintype "passive"))
      (node (ref "HDR-S") (pin "15") (pinfunction "15_15") (pintype "passive"))
    )
    (net (code "71") (name "XX3_P") (class "Default")
      (node (ref "C3") (pin "2") (pinfunction "2_2") (pintype "passive"))
      (node (ref "HDR-S") (pin "13") (pinfunction "13_13") (pintype "passive"))
    )
    (net (code "72") (name "XX4_N") (class "Default")
      (node (ref "C1") (pin "2") (pinfunction "2_2") (pintype "passive"))
      (node (ref "HDR-S") (pin "16") (pinfunction "16_16") (pintype "passive"))
    )
    (net (code "73") (name "XX4_P") (class "Default")
      (node (ref "C2") (pin "2") (pinfunction "2_2") (pintype "passive"))
      (node (ref "HDR-S") (pin "14") (pinfunction "14_14") (pintype "passive"))
    )
    (net (code "74") (name "unconnected-(U2-INT-Pad5)") (class "Default")
      (node (ref "U2") (pin "5") (pinfunction "INT_5") (pintype "output"))
    )
  )
)
